# mk312_control.net
KiCad netlist of a schematic drawn in EAGLE
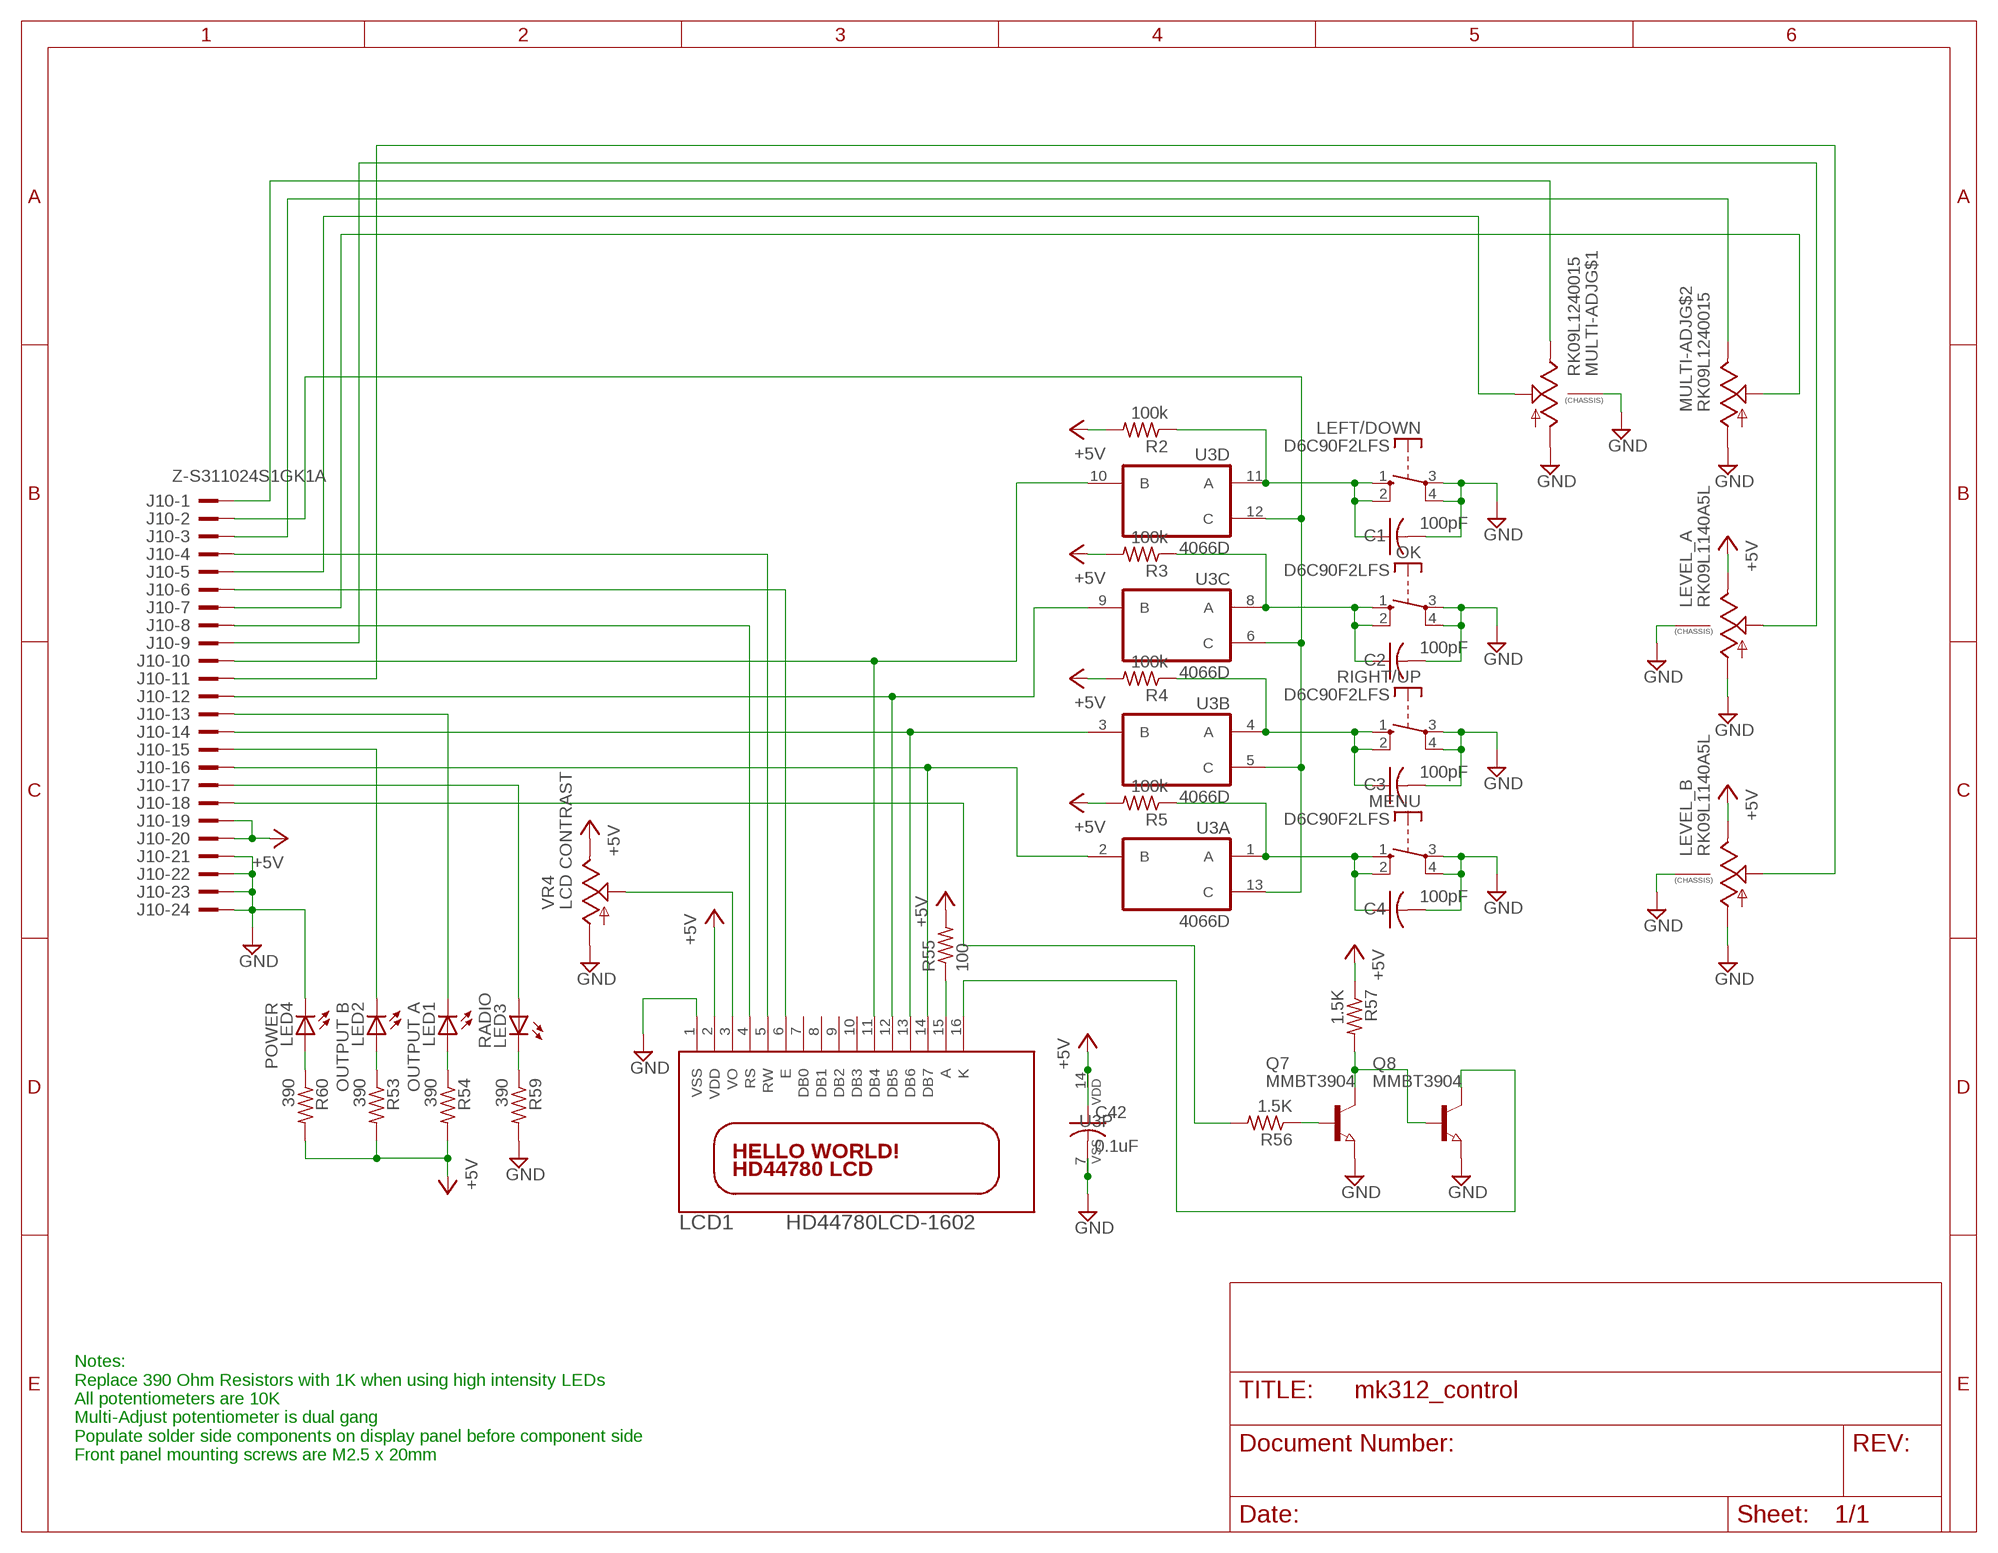
[diagram p0: schematic, sheet 1]

(export (version "E")
  (design (tool "Eeschema 10.0.6"))
  (components
    (comp (ref "C1")
      (value "100pF")
      (footprint "eagle-import:C0805")
      (libsource (lib "eagle-import") (part "rcl_334_C-USC0805"))
    )
    (comp (ref "C2")
      (value "100pF")
      (footprint "eagle-import:C0805")
      (libsource (lib "eagle-import") (part "rcl_334_C-USC0805"))
    )
    (comp (ref "C3")
      (value "100pF")
      (footprint "eagle-import:C0805")
      (libsource (lib "eagle-import") (part "rcl_334_C-USC0805"))
    )
    (comp (ref "C4")
      (value "100pF")
      (footprint "eagle-import:C0805")
      (libsource (lib "eagle-import") (part "rcl_334_C-USC0805"))
    )
    (comp (ref "C42")
      (value "0.1uF")
      (footprint "eagle-import:C0805")
      (libsource (lib "eagle-import") (part "C-USC0805"))
    )
    (comp (ref "J10")
      (value "Z-S311024S1GK1A")
      (footprint "eagle-import:PAK100_2500-24")
      (libsource (lib "eagle-import") (part "2524-"))
    )
    (comp (ref "LCD1")
      (value "HD44780LCD-1602")
      (footprint "eagle-import:LCD1602")
      (libsource (lib "eagle-import") (part "HD44780LCD-1602"))
    )
    (comp (ref "LED1")
      (value "OUTPUT A")
      (footprint "eagle-import:LED5MM")
      (libsource (lib "eagle-import") (part "LED5MM"))
    )
    (comp (ref "LED2")
      (value "OUTPUT B")
      (footprint "eagle-import:LED5MM")
      (libsource (lib "eagle-import") (part "LED5MM"))
    )
    (comp (ref "LED3")
      (value "RADIO")
      (footprint "eagle-import:LED5MM")
      (libsource (lib "eagle-import") (part "LED5MM"))
    )
    (comp (ref "LED4")
      (value "POWER")
      (footprint "eagle-import:LED5MM")
      (libsource (lib "eagle-import") (part "LED5MM"))
    )
    (comp (ref "LEFT/DOWN")
      (value "D6C90F2LFS")
      (footprint "eagle-import:DTE6K")
      (libsource (lib "eagle-import") (part "DTE6K"))
    )
    (comp (ref "LEVEL_A")
      (value "RK09L1140A5L")
      (footprint "eagle-import:9MM_SNAP-IN_POT")
      (libsource (lib "eagle-import") (part "9MM_SNAP-IN_POT_CHASSIS"))
    )
    (comp (ref "LEVEL_B")
      (value "RK09L1140A5L")
      (footprint "eagle-import:9MM_SNAP-IN_POT")
      (libsource (lib "eagle-import") (part "9MM_SNAP-IN_POT_CHASSIS"))
    )
    (comp (ref "MENU")
      (value "D6C90F2LFS")
      (footprint "eagle-import:DTE6K")
      (libsource (lib "eagle-import") (part "DTE6K"))
    )
    (comp (ref "MULTI-ADJ")
      (value "RK09L1240015")
      (footprint "eagle-import:DUAL_9MM_SNAP-IN_POT")
      (libsource (lib "eagle-import") (part "ALPHA-9MM-DUALPOT"))
    )
    (comp (ref "OK")
      (value "D6C90F2LFS")
      (footprint "eagle-import:DTE6K")
      (libsource (lib "eagle-import") (part "DTE6K"))
    )
    (comp (ref "Q7")
      (value "MMBT3904")
      (footprint "eagle-import:SOT23")
      (fields (field (name "LCSC_PART") "C20526"))
      (libsource (lib "eagle-import") (part "T_NPN__SOT23-BECMMBT3904_CHANGJ"))
    )
    (comp (ref "Q8")
      (value "MMBT3904")
      (footprint "eagle-import:SOT23")
      (fields (field (name "LCSC_PART") "C20526"))
      (libsource (lib "eagle-import") (part "T_NPN__SOT23-BECMMBT3904_CHANGJ"))
    )
    (comp (ref "R2")
      (value "100k")
      (footprint "eagle-import:R0805")
      (libsource (lib "eagle-import") (part "rcl_334_R-US_R0805"))
    )
    (comp (ref "R3")
      (value "100k")
      (footprint "eagle-import:R0805")
      (libsource (lib "eagle-import") (part "rcl_334_R-US_R0805"))
    )
    (comp (ref "R4")
      (value "100k")
      (footprint "eagle-import:R0805")
      (libsource (lib "eagle-import") (part "rcl_334_R-US_R0805"))
    )
    (comp (ref "R5")
      (value "100k")
      (footprint "eagle-import:R0805")
      (libsource (lib "eagle-import") (part "rcl_334_R-US_R0805"))
    )
    (comp (ref "R53")
      (value "390")
      (footprint "eagle-import:R0805")
      (libsource (lib "eagle-import") (part "R-US_R0805"))
    )
    (comp (ref "R54")
      (value "390")
      (footprint "eagle-import:R0805")
      (libsource (lib "eagle-import") (part "R-US_R0805"))
    )
    (comp (ref "R55")
      (value "100")
      (footprint "eagle-import:R0805")
      (libsource (lib "eagle-import") (part "R-US_R0805"))
    )
    (comp (ref "R56")
      (value "1.5K")
      (footprint "eagle-import:R0805")
      (libsource (lib "eagle-import") (part "R-US_R0805"))
    )
    (comp (ref "R57")
      (value "1.5K")
      (footprint "eagle-import:R0805")
      (libsource (lib "eagle-import") (part "R-US_R0805"))
    )
    (comp (ref "R59")
      (value "390")
      (footprint "eagle-import:R0805")
      (libsource (lib "eagle-import") (part "R-US_R0805"))
    )
    (comp (ref "R60")
      (value "390")
      (footprint "eagle-import:R0805")
      (libsource (lib "eagle-import") (part "R-US_R0805"))
    )
    (comp (ref "RIGHT/UP")
      (value "D6C90F2LFS")
      (footprint "eagle-import:DTE6K")
      (libsource (lib "eagle-import") (part "DTE6K"))
    )
    (comp (ref "U3")
      (value "4066D")
      (footprint "eagle-import:SO14")
      (libsource (lib "eagle-import") (part "4066D"))
    )
    (comp (ref "VR4")
      (value "LCD CONTRAST")
      (footprint "eagle-import:B25P")
      (libsource (lib "eagle-import") (part "TRIM_US-B25P"))
    )
  )
  (nets
    (net (code "1") (name "+5V") (class "Default")
      (node (ref "C42") (pin "1") (pinfunction "1_1") (pintype "passive"))
      (node (ref "J10") (pin "19") (pinfunction "KL_19") (pintype "passive"))
      (node (ref "J10") (pin "20") (pinfunction "KL_20") (pintype "passive"))
      (node (ref "LCD1") (pin "2") (pinfunction "VDD_2") (pintype "power_in"))
      (node (ref "LEVEL_A") (pin "3") (pinfunction "E_3") (pintype "passive"))
      (node (ref "LEVEL_B") (pin "3") (pinfunction "E_3") (pintype "passive"))
      (node (ref "R2") (pin "2") (pinfunction "2_2") (pintype "passive"))
      (node (ref "R3") (pin "2") (pinfunction "2_2") (pintype "passive"))
      (node (ref "R4") (pin "2") (pinfunction "2_2") (pintype "passive"))
      (node (ref "R5") (pin "2") (pinfunction "2_2") (pintype "passive"))
      (node (ref "R53") (pin "2") (pinfunction "2_2") (pintype "passive"))
      (node (ref "R54") (pin "2") (pinfunction "2_2") (pintype "passive"))
      (node (ref "R55") (pin "2") (pinfunction "2_2") (pintype "passive"))
      (node (ref "R57") (pin "1") (pinfunction "1_1") (pintype "passive"))
      (node (ref "R60") (pin "2") (pinfunction "2_2") (pintype "passive"))
      (node (ref "U3") (pin "14") (pinfunction "VDD_14") (pintype "power_in"))
      (node (ref "VR4") (pin "E") (pinfunction "E_E") (pintype "passive"))
    )
    (net (code "2") (name "GND") (class "Default")
      (node (ref "C1") (pin "2") (pinfunction "2_2") (pintype "passive"))
      (node (ref "C2") (pin "2") (pinfunction "2_2") (pintype "passive"))
      (node (ref "C3") (pin "2") (pinfunction "2_2") (pintype "passive"))
      (node (ref "C4") (pin "2") (pinfunction "2_2") (pintype "passive"))
      (node (ref "C42") (pin "2") (pinfunction "2_2") (pintype "passive"))
      (node (ref "J10") (pin "21") (pinfunction "KL_21") (pintype "passive"))
      (node (ref "J10") (pin "22") (pinfunction "KL_22") (pintype "passive"))
      (node (ref "J10") (pin "23") (pinfunction "KL_23") (pintype "passive"))
      (node (ref "J10") (pin "24") (pinfunction "KL_24") (pintype "passive"))
      (node (ref "LCD1") (pin "1") (pinfunction "VSS_1") (pintype "power_in"))
      (node (ref "LED4") (pin "K") (pinfunction "C_K") (pintype "passive"))
      (node (ref "LEFT/DOWN") (pin "3") (pinfunction "P_3") (pintype "passive"))
      (node (ref "LEFT/DOWN") (pin "4") (pinfunction "P_4") (pintype "passive"))
      (node (ref "LEVEL_A") (pin "1") (pinfunction "A_1") (pintype "passive"))
      (node (ref "LEVEL_A") (pin "CHASSIS2") (pinfunction "P$1_CHASSIS2") (pintype "passive"))
      (node (ref "LEVEL_B") (pin "1") (pinfunction "A_1") (pintype "passive"))
      (node (ref "LEVEL_B") (pin "CHASSIS2") (pinfunction "P$1_CHASSIS2") (pintype "passive"))
      (node (ref "MENU") (pin "3") (pinfunction "P_3") (pintype "passive"))
      (node (ref "MENU") (pin "4") (pinfunction "P_4") (pintype "passive"))
      (node (ref "MULTI-ADJ") (pin "1") (pinfunction "A_1") (pintype "passive"))
      (node (ref "MULTI-ADJ") (pin "1B") (pinfunction "A_1B") (pintype "passive"))
      (node (ref "MULTI-ADJ") (pin "CHASSIS1") (pinfunction "P$1_CHASSIS1") (pintype "passive"))
      (node (ref "MULTI-ADJ") (pin "CHASSIS2") (pinfunction "P$1_CHASSIS2") (pintype "passive"))
      (node (ref "OK") (pin "3") (pinfunction "P_3") (pintype "passive"))
      (node (ref "OK") (pin "4") (pinfunction "P_4") (pintype "passive"))
      (node (ref "Q7") (pin "2") (pinfunction "E_2") (pintype "passive"))
      (node (ref "Q8") (pin "2") (pinfunction "E_2") (pintype "passive"))
      (node (ref "R59") (pin "2") (pinfunction "2_2") (pintype "passive"))
      (node (ref "RIGHT/UP") (pin "3") (pinfunction "P_3") (pintype "passive"))
      (node (ref "RIGHT/UP") (pin "4") (pinfunction "P_4") (pintype "passive"))
      (node (ref "U3") (pin "7") (pinfunction "VSS_7") (pintype "power_in"))
      (node (ref "VR4") (pin "A") (pinfunction "A_A") (pintype "passive"))
    )
    (net (code "3") (name "Net-(J10A-KL)") (class "Default")
      (node (ref "J10") (pin "1") (pinfunction "KL_1") (pintype "passive"))
      (node (ref "MULTI-ADJ") (pin "3") (pinfunction "E_3") (pintype "passive"))
    )
    (net (code "4") (name "Net-(J10B-KL)") (class "Default")
      (node (ref "J10") (pin "10") (pinfunction "KL_10") (pintype "passive"))
      (node (ref "LCD1") (pin "11") (pinfunction "DB4_11") (pintype "bidirectional"))
      (node (ref "U3") (pin "10") (pinfunction "B_10") (pintype "tri_state"))
    )
    (net (code "5") (name "Net-(J10C-KL)") (class "Default")
      (node (ref "J10") (pin "11") (pinfunction "KL_11") (pintype "passive"))
      (node (ref "LEVEL_B") (pin "2") (pinfunction "S_2") (pintype "passive"))
    )
    (net (code "6") (name "Net-(J10D-KL)") (class "Default")
      (node (ref "J10") (pin "12") (pinfunction "KL_12") (pintype "passive"))
      (node (ref "LCD1") (pin "12") (pinfunction "DB5_12") (pintype "bidirectional"))
      (node (ref "U3") (pin "9") (pinfunction "B_9") (pintype "tri_state"))
    )
    (net (code "7") (name "Net-(J10E-KL)") (class "Default")
      (node (ref "J10") (pin "13") (pinfunction "KL_13") (pintype "passive"))
      (node (ref "LED1") (pin "K") (pinfunction "C_K") (pintype "passive"))
    )
    (net (code "8") (name "Net-(J10F-KL)") (class "Default")
      (node (ref "J10") (pin "14") (pinfunction "KL_14") (pintype "passive"))
      (node (ref "LCD1") (pin "13") (pinfunction "DB6_13") (pintype "bidirectional"))
      (node (ref "U3") (pin "3") (pinfunction "B_3") (pintype "tri_state"))
    )
    (net (code "9") (name "Net-(J10G-KL)") (class "Default")
      (node (ref "J10") (pin "15") (pinfunction "KL_15") (pintype "passive"))
      (node (ref "LED2") (pin "K") (pinfunction "C_K") (pintype "passive"))
    )
    (net (code "10") (name "Net-(J10H-KL)") (class "Default")
      (node (ref "J10") (pin "16") (pinfunction "KL_16") (pintype "passive"))
      (node (ref "LCD1") (pin "14") (pinfunction "DB7_14") (pintype "bidirectional"))
      (node (ref "U3") (pin "2") (pinfunction "B_2") (pintype "tri_state"))
    )
    (net (code "11") (name "Net-(J10I-KL)") (class "Default")
      (node (ref "J10") (pin "17") (pinfunction "KL_17") (pintype "passive"))
      (node (ref "LED3") (pin "A") (pinfunction "A_A") (pintype "passive"))
    )
    (net (code "12") (name "Net-(J10J-KL)") (class "Default")
      (node (ref "J10") (pin "18") (pinfunction "KL_18") (pintype "passive"))
      (node (ref "R56") (pin "2") (pinfunction "2_2") (pintype "passive"))
    )
    (net (code "13") (name "Net-(J10L-KL)") (class "Default")
      (node (ref "J10") (pin "2") (pinfunction "KL_2") (pintype "passive"))
      (node (ref "U3") (pin "12") (pinfunction "C_12") (pintype "input"))
      (node (ref "U3") (pin "13") (pinfunction "C_13") (pintype "input"))
      (node (ref "U3") (pin "5") (pinfunction "C_5") (pintype "input"))
      (node (ref "U3") (pin "6") (pinfunction "C_6") (pintype "input"))
    )
    (net (code "14") (name "Net-(J10R-KL)") (class "Default")
      (node (ref "J10") (pin "3") (pinfunction "KL_3") (pintype "passive"))
      (node (ref "MULTI-ADJ") (pin "3B") (pinfunction "E_3B") (pintype "passive"))
    )
    (net (code "15") (name "Net-(J10S-KL)") (class "Default")
      (node (ref "J10") (pin "4") (pinfunction "KL_4") (pintype "passive"))
      (node (ref "LCD1") (pin "5") (pinfunction "RW_5") (pintype "input"))
    )
    (net (code "16") (name "Net-(J10T-KL)") (class "Default")
      (node (ref "J10") (pin "5") (pinfunction "KL_5") (pintype "passive"))
      (node (ref "MULTI-ADJ") (pin "2") (pinfunction "S_2") (pintype "passive"))
    )
    (net (code "17") (name "Net-(J10U-KL)") (class "Default")
      (node (ref "J10") (pin "6") (pinfunction "KL_6") (pintype "passive"))
      (node (ref "LCD1") (pin "6") (pinfunction "E_6") (pintype "input"))
    )
    (net (code "18") (name "Net-(J10V-KL)") (class "Default")
      (node (ref "J10") (pin "7") (pinfunction "KL_7") (pintype "passive"))
      (node (ref "MULTI-ADJ") (pin "2B") (pinfunction "S_2B") (pintype "passive"))
    )
    (net (code "19") (name "Net-(J10W-KL)") (class "Default")
      (node (ref "J10") (pin "8") (pinfunction "KL_8") (pintype "passive"))
      (node (ref "LCD1") (pin "4") (pinfunction "RS_4") (pintype "input"))
    )
    (net (code "20") (name "Net-(J10X-KL)") (class "Default")
      (node (ref "J10") (pin "9") (pinfunction "KL_9") (pintype "passive"))
      (node (ref "LEVEL_A") (pin "2") (pinfunction "S_2") (pintype "passive"))
    )
    (net (code "21") (name "Net-(LCD1-A)") (class "Default")
      (node (ref "LCD1") (pin "15") (pinfunction "A_15") (pintype "input"))
      (node (ref "R55") (pin "1") (pinfunction "1_1") (pintype "passive"))
    )
    (net (code "22") (name "Net-(LCD1-K)") (class "Default")
      (node (ref "LCD1") (pin "16") (pinfunction "K_16") (pintype "input"))
      (node (ref "Q8") (pin "3") (pinfunction "C_3") (pintype "passive"))
    )
    (net (code "23") (name "Net-(LCD1-VO)") (class "Default")
      (node (ref "LCD1") (pin "3") (pinfunction "VO_3") (pintype "input"))
      (node (ref "VR4") (pin "S") (pinfunction "S_S") (pintype "passive"))
    )
    (net (code "24") (name "Net-(LED1-PadA)") (class "Default")
      (node (ref "LED1") (pin "A") (pinfunction "A_A") (pintype "passive"))
      (node (ref "R54") (pin "1") (pinfunction "1_1") (pintype "passive"))
    )
    (net (code "25") (name "Net-(LED2-PadA)") (class "Default")
      (node (ref "LED2") (pin "A") (pinfunction "A_A") (pintype "passive"))
      (node (ref "R53") (pin "1") (pinfunction "1_1") (pintype "passive"))
    )
    (net (code "26") (name "Net-(LED3-C)") (class "Default")
      (node (ref "LED3") (pin "K") (pinfunction "C_K") (pintype "passive"))
      (node (ref "R59") (pin "1") (pinfunction "1_1") (pintype "passive"))
    )
    (net (code "27") (name "Net-(LED4-PadA)") (class "Default")
      (node (ref "LED4") (pin "A") (pinfunction "A_A") (pintype "passive"))
      (node (ref "R60") (pin "1") (pinfunction "1_1") (pintype "passive"))
    )
    (net (code "28") (name "Net-(Q7-B)") (class "Default")
      (node (ref "Q7") (pin "1") (pinfunction "B_1") (pintype "passive"))
      (node (ref "R56") (pin "1") (pinfunction "1_1") (pintype "passive"))
    )
    (net (code "29") (name "Net-(Q7-C)") (class "Default")
      (node (ref "Q7") (pin "3") (pinfunction "C_3") (pintype "passive"))
      (node (ref "Q8") (pin "1") (pinfunction "B_1") (pintype "passive"))
      (node (ref "R57") (pin "2") (pinfunction "2_2") (pintype "passive"))
    )
    (net (code "30") (name "Net-(U3A-A)") (class "Default")
      (node (ref "C4") (pin "1") (pinfunction "1_1") (pintype "passive"))
      (node (ref "MENU") (pin "1") (pinfunction "S_1") (pintype "passive"))
      (node (ref "MENU") (pin "2") (pinfunction "S_2") (pintype "passive"))
      (node (ref "R5") (pin "1") (pinfunction "1_1") (pintype "passive"))
      (node (ref "U3") (pin "1") (pinfunction "A_1") (pintype "tri_state"))
    )
    (net (code "31") (name "Net-(U3B-A)") (class "Default")
      (node (ref "C3") (pin "1") (pinfunction "1_1") (pintype "passive"))
      (node (ref "R4") (pin "1") (pinfunction "1_1") (pintype "passive"))
      (node (ref "RIGHT/UP") (pin "1") (pinfunction "S_1") (pintype "passive"))
      (node (ref "RIGHT/UP") (pin "2") (pinfunction "S_2") (pintype "passive"))
      (node (ref "U3") (pin "4") (pinfunction "A_4") (pintype "tri_state"))
    )
    (net (code "32") (name "Net-(U3C-A)") (class "Default")
      (node (ref "C2") (pin "1") (pinfunction "1_1") (pintype "passive"))
      (node (ref "OK") (pin "1") (pinfunction "S_1") (pintype "passive"))
      (node (ref "OK") (pin "2") (pinfunction "S_2") (pintype "passive"))
      (node (ref "R3") (pin "1") (pinfunction "1_1") (pintype "passive"))
      (node (ref "U3") (pin "8") (pinfunction "A_8") (pintype "tri_state"))
    )
    (net (code "33") (name "Net-(U3D-A)") (class "Default")
      (node (ref "C1") (pin "1") (pinfunction "1_1") (pintype "passive"))
      (node (ref "LEFT/DOWN") (pin "1") (pinfunction "S_1") (pintype "passive"))
      (node (ref "LEFT/DOWN") (pin "2") (pinfunction "S_2") (pintype "passive"))
      (node (ref "R2") (pin "1") (pinfunction "1_1") (pintype "passive"))
      (node (ref "U3") (pin "11") (pinfunction "A_11") (pintype "tri_state"))
    )
    (net (code "34") (name "unconnected-(LCD1-DB0-Pad7)") (class "Default")
      (node (ref "LCD1") (pin "7") (pinfunction "DB0_7") (pintype "bidirectional"))
    )
    (net (code "35") (name "unconnected-(LCD1-DB1-Pad8)") (class "Default")
      (node (ref "LCD1") (pin "8") (pinfunction "DB1_8") (pintype "bidirectional"))
    )
    (net (code "36") (name "unconnected-(LCD1-DB2-Pad9)") (class "Default")
      (node (ref "LCD1") (pin "9") (pinfunction "DB2_9") (pintype "bidirectional"))
    )
    (net (code "37") (name "unconnected-(LCD1-DB3-Pad10)") (class "Default")
      (node (ref "LCD1") (pin "10") (pinfunction "DB3_10") (pintype "bidirectional"))
    )
  )
)
